# SENSORS.net
KiCad netlist of a schematic drawn in Altium Designer
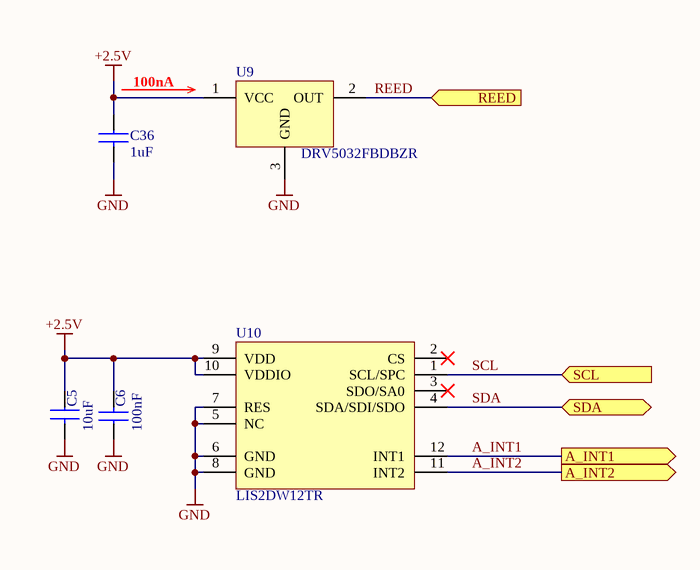
[diagram p0: SENSORS.SchDoc]

(export (version "E")
  (design (tool "Eeschema 10.0.6"))
  (components
    (comp (ref "C5")
      (value "10uF")
      (footprint "CAP0603")
      (description "Cap Ceramic 10uF 10V X5R 10% SMD 0603 85C Paper T/R")
      (fields
        (field (name "MANUFACTURER") "Samsung")
        (field (name "MANUFACTURER PART NUMBER") "CL10A106KP8NNNC")
      )
      (libsource (lib "Passive") (part "C - 10uF/10V"))
    )
    (comp (ref "C6")
      (value "100nF")
      (footprint "CAP0402")
      (fields
        (field (name "MANUFACTURER") "Multicomp")
        (field (name "MANUFACTURER PART NUMBER") "MC0402X104J160CT")
        (field (name "TOLERANCE") "5%")
      )
      (libsource (lib "Passive") (part "C - 100nF/0402"))
    )
    (comp (ref "C36")
      (value "1uF")
      (footprint "CAP0402")
      (description "CAP CER 1UF 10V 20% X5R 0402")
      (fields
        (field (name "MANUFACTURER") "Murata")
        (field (name "MANUFACTURER PART NUMBER") "GRM155R61A105ME15D")
      )
      (libsource (lib "Passive") (part "C - 1uF/0402"))
    )
    (comp (ref "U9")
      (value "DRV5032FBDBZR")
      (footprint "SOT23-3AL")
      (description "Board Mount Hall Effect/Magnetic Sensors LP HALL 32FBDBZR")
      (fields
        (field (name "MANUFACTURER") "TDK InvenSense")
        (field (name "MANUFACTURER PART NUMBER") "MPU-9250")
      )
      (libsource (lib "Active") (part "SEN - DRV5032FBDBZR"))
    )
    (comp (ref "U10")
      (value "LIS2DW12TR")
      (footprint "LGA-12")
      (description "MEMS Accelerometer, Digital, X, Y, Z, ± 2g, ± 4g, ± 8g, ± 16g, 1.62 V, 3.6 V")
      (fields
        (field (name "MANUFACTURER") "TDK InvenSense")
        (field (name "MANUFACTURER PART NUMBER") "MPU-9250")
      )
      (libsource (lib "Active") (part "SEN - LIS2DW12TR"))
    )
  )
  (nets
    (net (code "1") (name "+2.5V") (class "Default")
      (node (ref "C36") (pin "1") (pinfunction "1_1") (pintype "passive"))
      (node (ref "C5") (pin "1") (pinfunction "1_1") (pintype "passive"))
      (node (ref "C6") (pin "2") (pinfunction "2_2") (pintype "passive"))
      (node (ref "U10") (pin "10") (pinfunction "VDDIO_10") (pintype "passive"))
      (node (ref "U10") (pin "9") (pinfunction "VDD_9") (pintype "passive"))
      (node (ref "U9") (pin "1") (pinfunction "VCC_1") (pintype "passive"))
    )
    (net (code "2") (name "/A_INT1") (class "Default")
      (node (ref "U10") (pin "12") (pinfunction "INT1_12") (pintype "passive"))
    )
    (net (code "3") (name "/A_INT2") (class "Default")
      (node (ref "U10") (pin "11") (pinfunction "INT2_11") (pintype "passive"))
    )
    (net (code "4") (name "/REED") (class "Default")
      (node (ref "U9") (pin "2") (pinfunction "OUT_2") (pintype "passive"))
    )
    (net (code "5") (name "/SCL") (class "Default")
      (node (ref "U10") (pin "1") (pinfunction "SCL/SPC_1") (pintype "passive"))
    )
    (net (code "6") (name "/SDA") (class "Default")
      (node (ref "U10") (pin "4") (pinfunction "SDA/SDI/SDO_4") (pintype "passive"))
    )
    (net (code "7") (name "GND") (class "Default")
      (node (ref "C36") (pin "2") (pinfunction "2_2") (pintype "passive"))
      (node (ref "C5") (pin "2") (pinfunction "2_2") (pintype "passive"))
      (node (ref "C6") (pin "1") (pinfunction "1_1") (pintype "passive"))
      (node (ref "U10") (pin "5") (pinfunction "NC_5") (pintype "passive"))
      (node (ref "U10") (pin "6") (pinfunction "GND_6") (pintype "passive"))
      (node (ref "U10") (pin "7") (pinfunction "RES_7") (pintype "passive"))
      (node (ref "U10") (pin "8") (pinfunction "GND_8") (pintype "passive"))
      (node (ref "U9") (pin "3") (pinfunction "GND_3") (pintype "passive"))
    )
    (net (code "8") (name "unconnected-(U10-CS-Pad2)") (class "Default")
      (node (ref "U10") (pin "2") (pinfunction "CS_2") (pintype "passive+no_connect"))
    )
    (net (code "9") (name "unconnected-(U10-SDO{slash}SA0-Pad3)") (class "Default")
      (node (ref "U10") (pin "3") (pinfunction "SDO/SA0_3") (pintype "passive+no_connect"))
    )
  )
)
